# Precharge_circuit.net
KiCad netlist of a schematic drawn in Altium Designer
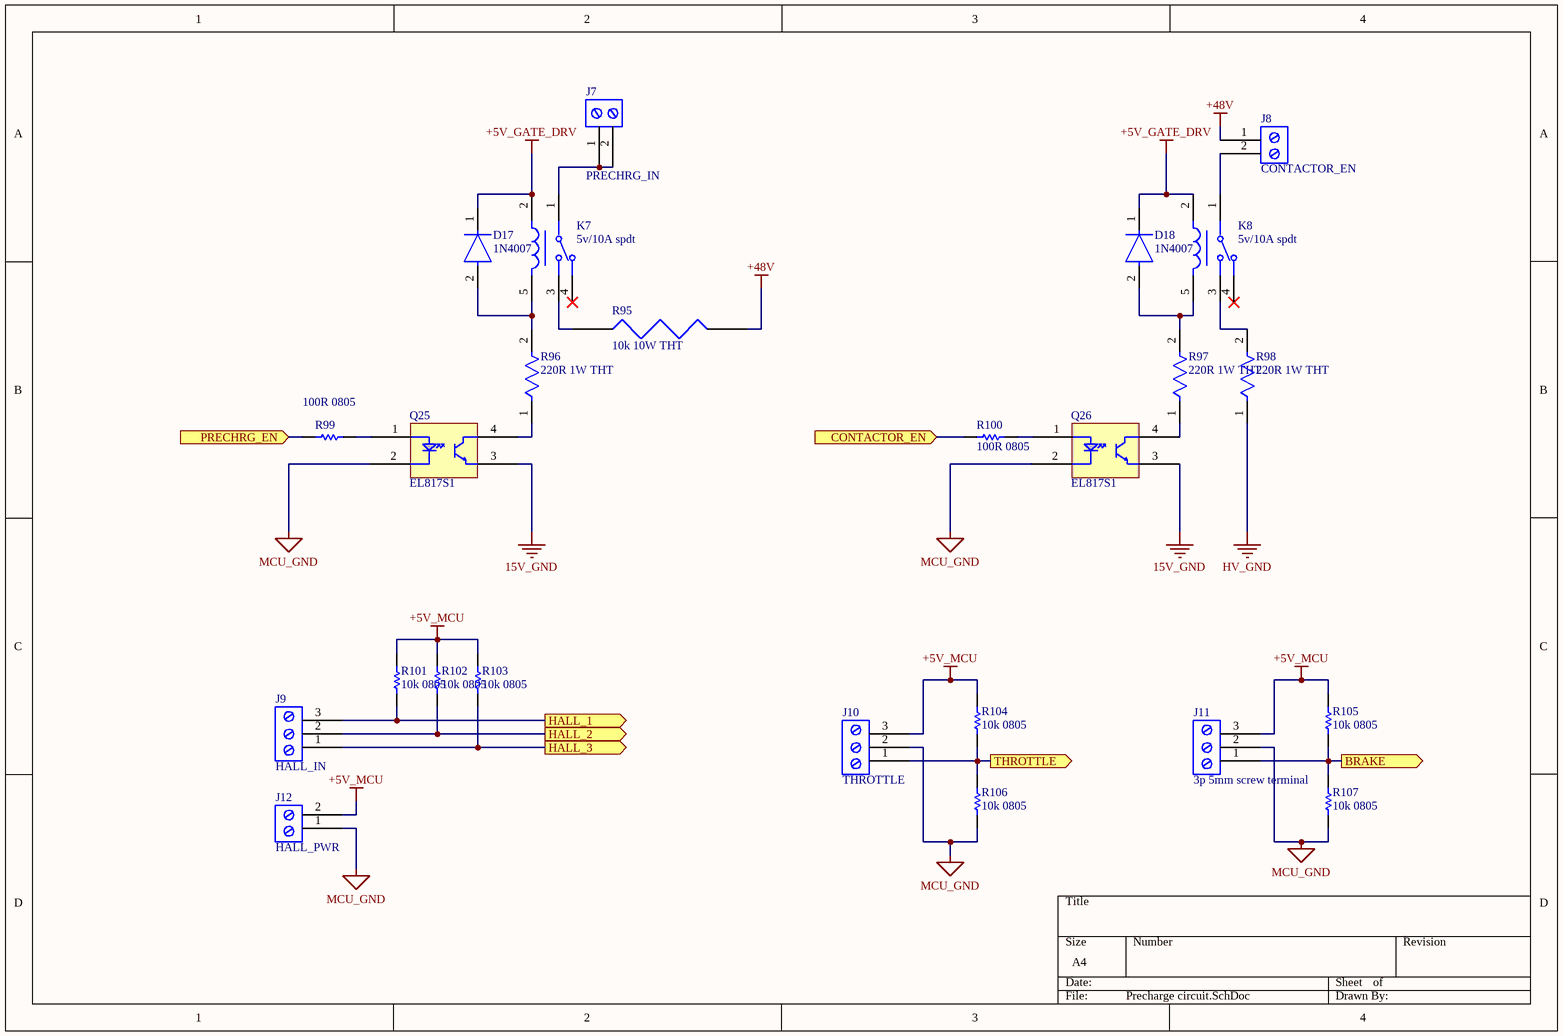
[diagram p0: Precharge circuit.SchDoc]

(export (version "E")
  (design (tool "Eeschema 10.0.6"))
  (components
    (comp (ref "D17")
      (value "1N4007")
      (footprint "FP-1N4007-MFG")
      (description "GOOD-ARK 1N4007 General Purpose Rectifier Diode – DO-41 Package")
      (fields
        (field (name "MANUFACTURER") "Diotec")
        (field (name "OCTOPART") "https://octopart.com/1n4007-diotec-4040411")
      )
      (libsource (lib "Altium Content Vault") (part "d7152d700b627762746794eb795d46e"))
    )
    (comp (ref "D18")
      (value "1N4007")
      (footprint "FP-1N4007-MFG")
      (description "GOOD-ARK 1N4007 General Purpose Rectifier Diode – DO-41 Package")
      (fields
        (field (name "MANUFACTURER") "Diotec")
        (field (name "OCTOPART") "https://octopart.com/1n4007-diotec-4040411")
      )
      (libsource (lib "Altium Content Vault") (part "d7152d700b627762746794eb795d46e"))
    )
    (comp (ref "J7")
      (value "PRECHRG_IN")
      (footprint "TERMINAL_5MM_2P")
      (description "XY127- 2 Pin Screw Terminal- 5mm Pitch")
      (libsource (lib "") (part "2p 5mm screw terminal_2"))
    )
    (comp (ref "J8")
      (value "CONTACTOR_EN")
      (footprint "TERMINAL_5MM_2P")
      (description "XY127- 2 Pin Screw Terminal- 5mm Pitch")
      (libsource (lib "") (part "2p 5mm screw terminal_1"))
    )
    (comp (ref "J9")
      (value "HALL_IN")
      (footprint "TERMINAL_5MM_3P")
      (description "XY127- 3 Pin Screw Terminal- 5mm Pitch")
      (libsource (lib "1kW_BLDC_Controller") (part "3p 5mm screw terminal"))
    )
    (comp (ref "J10")
      (value "THROTTLE")
      (footprint "TERMINAL_5MM_3P")
      (description "XY127- 3 Pin Screw Terminal- 5mm Pitch")
      (libsource (lib "1kW_BLDC_Controller") (part "3p 5mm screw terminal"))
    )
    (comp (ref "J11")
      (value "3p 5mm screw terminal")
      (footprint "TERMINAL_5MM_3P")
      (description "XY127- 3 Pin Screw Terminal- 5mm Pitch")
      (libsource (lib "1kW_BLDC_Controller") (part "3p 5mm screw terminal"))
    )
    (comp (ref "J12")
      (value "HALL_PWR")
      (footprint "TERMINAL_5MM_2P")
      (description "XY127- 2 Pin Screw Terminal- 5mm Pitch")
      (libsource (lib "1kW_BLDC_Controller") (part "2p 5mm screw terminal"))
    )
    (comp (ref "K7")
      (value "5v/10A spdt")
      (footprint "FP-G5LE-1-E-36-DC5-MFG")
      (description "HF3FF/005-1ZST – 05V 10A SPDT Relay – Hongfa")
      (libsource (lib "Altium Content Vault") (part "c03b8d08e5d02e70a6880f365e34168"))
    )
    (comp (ref "K8")
      (value "5v/10A spdt")
      (footprint "FP-G5LE-1-E-36-DC5-MFG")
      (description "HF3FF/005-1ZST – 05V 10A SPDT Relay – Hongfa")
      (libsource (lib "Altium Content Vault") (part "c03b8d08e5d02e70a6880f365e34168"))
    )
    (comp (ref "Q25")
      (value "EL817S1")
      (footprint "EL817S1")
      (description "EL817S1 (B) (TU) – F Optocoupler SMD-4 Cut Tape")
      (libsource (lib "1kW_BLDC_Controller") (part "EL817S1"))
    )
    (comp (ref "Q26")
      (value "EL817S1")
      (footprint "EL817S1")
      (description "EL817S1 (B) (TU) – F Optocoupler SMD-4 Cut Tape")
      (libsource (lib "1kW_BLDC_Controller") (part "EL817S1"))
    )
    (comp (ref "R95")
      (value "10k 10W THT")
      (footprint "R10W")
      (description "10K ohm 10W Fusible Cement Resistor")
      (libsource (lib "1kW_BLDC_Controller") (part "10k_10W_THT"))
    )
    (comp (ref "R96")
      (value "220R 1W THT")
      (footprint "R1WTHT")
      (description "220 Ohm 1 Watt Resistor 5% Tolerance")
      (libsource (lib "1kW_BLDC_Controller") (part "220R 1W THT"))
    )
    (comp (ref "R97")
      (value "220R 1W THT")
      (footprint "R1WTHT")
      (description "220 Ohm 1 Watt Resistor 5% Tolerance")
      (libsource (lib "1kW_BLDC_Controller") (part "220R 1W THT"))
    )
    (comp (ref "R98")
      (value "220R 1W THT")
      (footprint "R1WTHT")
      (description "220 Ohm 1 Watt Resistor 5% Tolerance")
      (libsource (lib "1kW_BLDC_Controller") (part "220R 1W THT"))
    )
    (comp (ref "R99")
      (value "100R 0805")
      (footprint "R0805")
      (description "100 ohm 1/4W Resistor 0805 Package")
      (libsource (lib "1kW_BLDC_Controller") (part "100R 0805"))
    )
    (comp (ref "R100")
      (value "100R 0805")
      (footprint "R0805")
      (description "100 ohm 1/4W Resistor 0805 Package")
      (libsource (lib "1kW_BLDC_Controller") (part "100R 0805"))
    )
    (comp (ref "R101")
      (value "10k 0805")
      (footprint "R0805")
      (description "10K Ohm 1/8 Watt Resistor 1% Tolerance RC0805FR-0710KL – 0805 Package")
      (libsource (lib "1kW_BLDC_Controller") (part "10k 0805"))
    )
    (comp (ref "R102")
      (value "10k 0805")
      (footprint "R0805")
      (description "10K Ohm 1/8 Watt Resistor 1% Tolerance RC0805FR-0710KL – 0805 Package")
      (libsource (lib "1kW_BLDC_Controller") (part "10k 0805"))
    )
    (comp (ref "R103")
      (value "10k 0805")
      (footprint "R0805")
      (description "10K Ohm 1/8 Watt Resistor 1% Tolerance RC0805FR-0710KL – 0805 Package")
      (libsource (lib "1kW_BLDC_Controller") (part "10k 0805"))
    )
    (comp (ref "R104")
      (value "10k 0805")
      (footprint "R0805")
      (description "10K Ohm 1/8 Watt Resistor 1% Tolerance RC0805FR-0710KL – 0805 Package")
      (libsource (lib "1kW_BLDC_Controller") (part "10k 0805"))
    )
    (comp (ref "R105")
      (value "10k 0805")
      (footprint "R0805")
      (description "10K Ohm 1/8 Watt Resistor 1% Tolerance RC0805FR-0710KL – 0805 Package")
      (libsource (lib "1kW_BLDC_Controller") (part "10k 0805"))
    )
    (comp (ref "R106")
      (value "10k 0805")
      (footprint "R0805")
      (description "10K Ohm 1/8 Watt Resistor 1% Tolerance RC0805FR-0710KL – 0805 Package")
      (libsource (lib "1kW_BLDC_Controller") (part "10k 0805"))
    )
    (comp (ref "R107")
      (value "10k 0805")
      (footprint "R0805")
      (description "10K Ohm 1/8 Watt Resistor 1% Tolerance RC0805FR-0710KL – 0805 Package")
      (libsource (lib "1kW_BLDC_Controller") (part "10k 0805"))
    )
  )
  (nets
    (net (code "1") (name "+5V_GATE_DRV") (class "Default")
      (node (ref "D17") (pin "1") (pinfunction "C_1") (pintype "passive"))
      (node (ref "D18") (pin "1") (pinfunction "C_1") (pintype "passive"))
      (node (ref "K7") (pin "2") (pinfunction "2_2") (pintype "passive"))
      (node (ref "K8") (pin "2") (pinfunction "2_2") (pintype "passive"))
    )
    (net (code "2") (name "+5V_MCU") (class "Default")
      (node (ref "J10") (pin "3") (pinfunction "3_3") (pintype "passive"))
      (node (ref "J11") (pin "3") (pinfunction "3_3") (pintype "passive"))
      (node (ref "J12") (pin "2") (pinfunction "2_2") (pintype "passive"))
      (node (ref "R101") (pin "2") (pinfunction "2_2") (pintype "passive"))
      (node (ref "R102") (pin "2") (pinfunction "2_2") (pintype "passive"))
      (node (ref "R103") (pin "2") (pinfunction "2_2") (pintype "passive"))
      (node (ref "R104") (pin "2") (pinfunction "2_2") (pintype "passive"))
      (node (ref "R105") (pin "2") (pinfunction "2_2") (pintype "passive"))
    )
    (net (code "3") (name "+48V") (class "Default")
      (node (ref "J8") (pin "1") (pinfunction "1_1") (pintype "passive"))
      (node (ref "R95") (pin "2") (pinfunction "2_2") (pintype "passive"))
    )
    (net (code "4") (name "/BRAKE") (class "Default")
      (node (ref "J11") (pin "1") (pinfunction "1_1") (pintype "passive"))
      (node (ref "R105") (pin "1") (pinfunction "1_1") (pintype "passive"))
      (node (ref "R107") (pin "2") (pinfunction "2_2") (pintype "passive"))
    )
    (net (code "5") (name "/CONTACTOR_EN") (class "Default")
      (node (ref "R100") (pin "1") (pinfunction "1_1") (pintype "passive"))
    )
    (net (code "6") (name "/HALL_1") (class "Default")
      (node (ref "J9") (pin "3") (pinfunction "3_3") (pintype "passive"))
      (node (ref "R101") (pin "1") (pinfunction "1_1") (pintype "passive"))
    )
    (net (code "7") (name "/HALL_2") (class "Default")
      (node (ref "J9") (pin "2") (pinfunction "2_2") (pintype "passive"))
      (node (ref "R102") (pin "1") (pinfunction "1_1") (pintype "passive"))
    )
    (net (code "8") (name "/HALL_3") (class "Default")
      (node (ref "J9") (pin "1") (pinfunction "1_1") (pintype "passive"))
      (node (ref "R103") (pin "1") (pinfunction "1_1") (pintype "passive"))
    )
    (net (code "9") (name "/PRECHRG_EN") (class "Default")
      (node (ref "R99") (pin "1") (pinfunction "1_1") (pintype "passive"))
    )
    (net (code "10") (name "/THROTTLE") (class "Default")
      (node (ref "J10") (pin "1") (pinfunction "1_1") (pintype "passive"))
      (node (ref "R104") (pin "1") (pinfunction "1_1") (pintype "passive"))
      (node (ref "R106") (pin "2") (pinfunction "2_2") (pintype "passive"))
    )
    (net (code "11") (name "15V_GND") (class "Default")
      (node (ref "Q25") (pin "3") (pinfunction "E_3") (pintype "passive"))
      (node (ref "Q26") (pin "3") (pinfunction "E_3") (pintype "passive"))
    )
    (net (code "12") (name "HV_GND") (class "Default")
      (node (ref "R98") (pin "1") (pinfunction "1_1") (pintype "passive"))
    )
    (net (code "13") (name "MCU_GND") (class "Default")
      (node (ref "J10") (pin "2") (pinfunction "2_2") (pintype "passive"))
      (node (ref "J11") (pin "2") (pinfunction "2_2") (pintype "passive"))
      (node (ref "J12") (pin "1") (pinfunction "1_1") (pintype "passive"))
      (node (ref "Q25") (pin "2") (pinfunction "K_2") (pintype "passive"))
      (node (ref "Q26") (pin "2") (pinfunction "K_2") (pintype "passive"))
      (node (ref "R106") (pin "1") (pinfunction "1_1") (pintype "passive"))
      (node (ref "R107") (pin "1") (pinfunction "1_1") (pintype "passive"))
    )
    (net (code "14") (name "Net-(D17-A)") (class "Default")
      (node (ref "D17") (pin "2") (pinfunction "A_2") (pintype "passive"))
      (node (ref "K7") (pin "5") (pinfunction "5_5") (pintype "passive"))
      (node (ref "R96") (pin "2") (pinfunction "2_2") (pintype "passive"))
    )
    (net (code "15") (name "Net-(D18-A)") (class "Default")
      (node (ref "D18") (pin "2") (pinfunction "A_2") (pintype "passive"))
      (node (ref "K8") (pin "5") (pinfunction "5_5") (pintype "passive"))
      (node (ref "R97") (pin "2") (pinfunction "2_2") (pintype "passive"))
    )
    (net (code "16") (name "Net-(J7-Pad1)") (class "Default")
      (node (ref "J7") (pin "1") (pinfunction "1_1") (pintype "passive"))
      (node (ref "J7") (pin "2") (pinfunction "2_2") (pintype "passive"))
      (node (ref "K7") (pin "1") (pinfunction "1_1") (pintype "passive"))
    )
    (net (code "17") (name "Net-(J8-Pad2)") (class "Default")
      (node (ref "J8") (pin "2") (pinfunction "2_2") (pintype "passive"))
      (node (ref "K8") (pin "1") (pinfunction "1_1") (pintype "passive"))
    )
    (net (code "18") (name "Net-(K7-Pad3)") (class "Default")
      (node (ref "K7") (pin "3") (pinfunction "3_3") (pintype "passive"))
      (node (ref "R95") (pin "1") (pinfunction "1_1") (pintype "passive"))
    )
    (net (code "19") (name "Net-(K8-Pad3)") (class "Default")
      (node (ref "K8") (pin "3") (pinfunction "3_3") (pintype "passive"))
      (node (ref "R98") (pin "2") (pinfunction "2_2") (pintype "passive"))
    )
    (net (code "20") (name "Net-(Q25-A)") (class "Default")
      (node (ref "Q25") (pin "1") (pinfunction "A_1") (pintype "passive"))
      (node (ref "R99") (pin "2") (pinfunction "2_2") (pintype "passive"))
    )
    (net (code "21") (name "Net-(Q25-C)") (class "Default")
      (node (ref "Q25") (pin "4") (pinfunction "C_4") (pintype "passive"))
      (node (ref "R96") (pin "1") (pinfunction "1_1") (pintype "passive"))
    )
    (net (code "22") (name "Net-(Q26-A)") (class "Default")
      (node (ref "Q26") (pin "1") (pinfunction "A_1") (pintype "passive"))
      (node (ref "R100") (pin "2") (pinfunction "2_2") (pintype "passive"))
    )
    (net (code "23") (name "Net-(Q26-C)") (class "Default")
      (node (ref "Q26") (pin "4") (pinfunction "C_4") (pintype "passive"))
      (node (ref "R97") (pin "1") (pinfunction "1_1") (pintype "passive"))
    )
    (net (code "24") (name "unconnected-(K7-Pad4)") (class "Default")
      (node (ref "K7") (pin "4") (pinfunction "4_4") (pintype "passive+no_connect"))
    )
    (net (code "25") (name "unconnected-(K8-Pad4)") (class "Default")
      (node (ref "K8") (pin "4") (pinfunction "4_4") (pintype "passive+no_connect"))
    )
  )
)
